# 02_USB2UART.net
KiCad netlist of a schematic drawn in Altium Designer
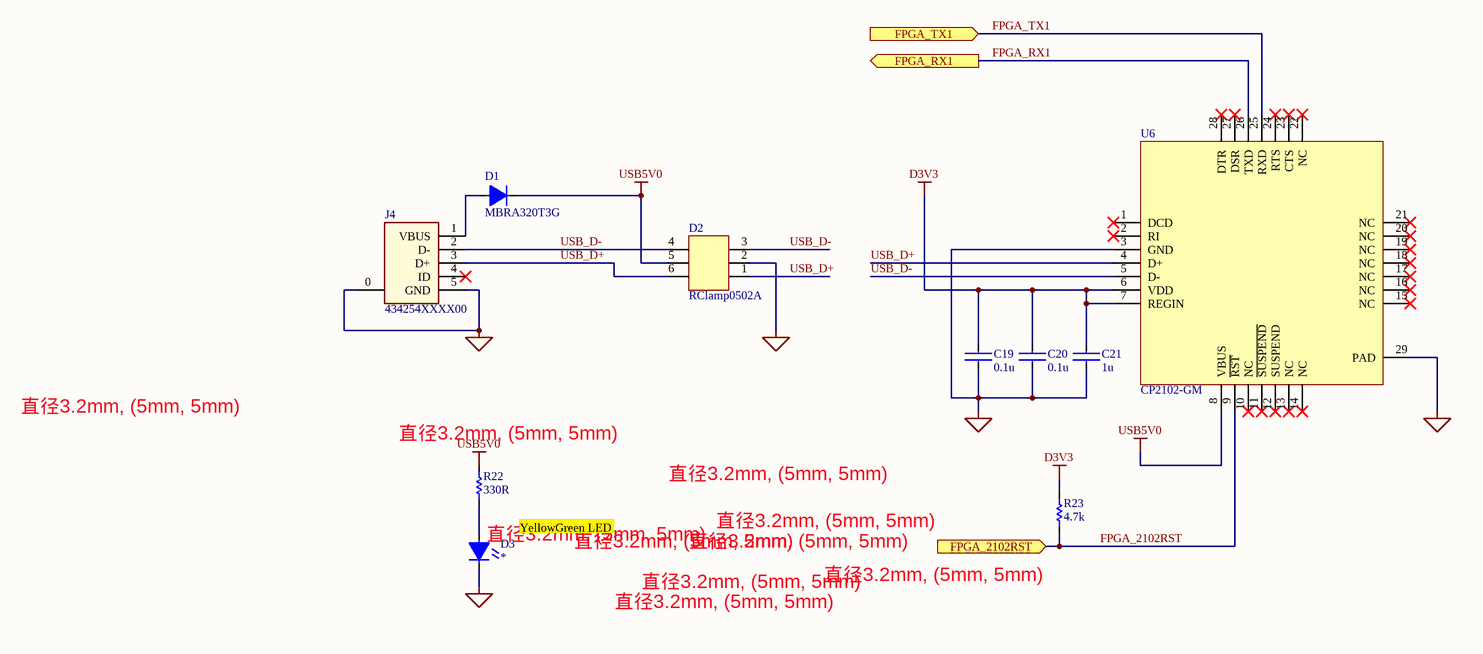
[diagram p0: 02_USB2UART.SchDoc]

(export (version "E")
  (design (tool "Eeschema 10.0.6"))
  (components
    (comp (ref "C19")
      (value "0.1u")
      (footprint "C0402")
      (description "CAP,Ceramic,X7R,10%,16V,0.1uF,0402")
      (libsource (lib "AD15_libpkg") (part "CAP011"))
    )
    (comp (ref "C20")
      (value "0.1u")
      (footprint "C0402")
      (description "CAP,Ceramic,X7R,10%,16V,0.1uF,0402")
      (libsource (lib "AD15_libpkg") (part "CAP011"))
    )
    (comp (ref "C21")
      (value "1u")
      (footprint "CAPC1608X09N_C0603")
      (description "CAP,Ceramic,X7R,10%,16V,1uF,0603")
      (libsource (lib "AD15_libpkg") (part "CAP12"))
    )
    (comp (ref "D1")
      (value "MBRA320T3G")
      (footprint "DIOM4326X23N_SMA")
      (description "Schottky Barrier Rectifier,20V,3A,SMA")
      (libsource (lib "AD15_libpkg") (part "MBRA320T3G"))
    )
    (comp (ref "D2")
      (value "RClamp0502A")
      (footprint "SOTFL50P162X60-6N_RClamp0502A")
      (description "TVS array,0.9pF,5V,SC89")
      (libsource (lib "altium-import") (part "root_2_RClamp0502A_"))
    )
    (comp (ref "D3")
      (value "*")
      (footprint "LED0603")
      (description "LED,Yellow Green,2V,20mA,0603")
      (libsource (lib "AD15_libpkg") (part "LED YellowGreen0603"))
    )
    (comp (ref "J4")
      (value "434254XXXX00")
      (footprint "434254XXXX00")
      (description "Mini-USB Receptacle,5-Pin,0.8mm Pitch,SMD")
      (libsource (lib "AD15_libpkg") (part "434254XXXX00"))
    )
    (comp (ref "R22")
      (value "330R")
      (footprint "R0402")
      (description "RES,330R,1%,1/16W,0402")
      (libsource (lib "AD15_libpkg") (part "RES0111"))
    )
    (comp (ref "R23")
      (value "4.7k")
      (footprint "R0402")
      (description "RES,4.7k,1%,1/16W,0402")
      (libsource (lib "R0402") (part "RES015"))
    )
    (comp (ref "U6")
      (value "CP2102-GM")
      (footprint "QFN50P500X500X100_HS-29N_CP2012GM")
      (description "IC,USB to UART bridge,QFN28")
      (libsource (lib "AD15_libpkg") (part "CP2102-GM"))
    )
  )
  (nets
    (net (code "1") (name "/FPGA_2102RST") (class "Default")
      (node (ref "R23") (pin "1") (pinfunction "0_1") (pintype "passive"))
      (node (ref "U6") (pin "9") (pinfunction "~{RST}_9") (pintype "passive"))
    )
    (net (code "2") (name "/FPGA_RX1") (class "Default")
      (node (ref "U6") (pin "26") (pinfunction "TXD_26") (pintype "passive"))
    )
    (net (code "3") (name "/FPGA_TX1") (class "Default")
      (node (ref "U6") (pin "25") (pinfunction "RXD_25") (pintype "passive"))
    )
    (net (code "4") (name "/USB_D+") (class "Default")
      (node (ref "D2") (pin "1") (pinfunction "0_1") (pintype "passive"))
      (node (ref "D2") (pin "6") (pinfunction "5_6") (pintype "passive"))
      (node (ref "J4") (pin "3") (pinfunction "D+_3") (pintype "passive"))
      (node (ref "U6") (pin "4") (pinfunction "D+_4") (pintype "passive"))
    )
    (net (code "5") (name "/USB_D-") (class "Default")
      (node (ref "D2") (pin "3") (pinfunction "2_3") (pintype "passive"))
      (node (ref "D2") (pin "4") (pinfunction "3_4") (pintype "passive"))
      (node (ref "J4") (pin "2") (pinfunction "D-_2") (pintype "passive"))
      (node (ref "U6") (pin "5") (pinfunction "D-_5") (pintype "passive"))
    )
    (net (code "6") (name "D3V3") (class "Default")
      (node (ref "C19") (pin "1") (pinfunction "0_1") (pintype "passive"))
      (node (ref "C20") (pin "1") (pinfunction "0_1") (pintype "passive"))
      (node (ref "C21") (pin "1") (pinfunction "0_1") (pintype "passive"))
      (node (ref "R23") (pin "2") (pinfunction "2_2") (pintype "passive"))
      (node (ref "U6") (pin "6") (pinfunction "VDD_6") (pintype "passive"))
      (node (ref "U6") (pin "7") (pinfunction "REGIN_7") (pintype "passive"))
    )
    (net (code "7") (name "GND") (class "Default")
      (node (ref "C19") (pin "2") (pinfunction "1_2") (pintype "passive"))
      (node (ref "C20") (pin "2") (pinfunction "1_2") (pintype "passive"))
      (node (ref "C21") (pin "2") (pinfunction "1_2") (pintype "passive"))
      (node (ref "D2") (pin "2") (pinfunction "1_2") (pintype "passive"))
      (node (ref "D3") (pin "2") (pinfunction "L21_2") (pintype "passive"))
      (node (ref "J4") (pin "0") (pintype "passive"))
      (node (ref "J4") (pin "5") (pinfunction "GND_5") (pintype "passive"))
      (node (ref "U6") (pin "29") (pinfunction "PAD_29") (pintype "passive"))
      (node (ref "U6") (pin "3") (pinfunction "GND_3") (pintype "passive"))
    )
    (net (code "8") (name "Net-(D1-A)") (class "Default")
      (node (ref "D1") (pin "1") (pinfunction "A_1") (pintype "passive"))
      (node (ref "J4") (pin "1") (pinfunction "VBUS_1") (pintype "passive"))
    )
    (net (code "9") (name "Net-(D3-L20)") (class "Default")
      (node (ref "D3") (pin "1") (pinfunction "L20_1") (pintype "passive"))
      (node (ref "R22") (pin "1") (pinfunction "0_1") (pintype "passive"))
    )
    (net (code "10") (name "USB5V0") (class "Default")
      (node (ref "D1") (pin "2") (pinfunction "K_2") (pintype "passive"))
      (node (ref "D2") (pin "5") (pinfunction "4_5") (pintype "passive"))
      (node (ref "R22") (pin "2") (pinfunction "2_2") (pintype "passive"))
      (node (ref "U6") (pin "8") (pinfunction "VBUS_8") (pintype "passive"))
    )
    (net (code "11") (name "unconnected-(J4-ID-Pad4)") (class "Default")
      (node (ref "J4") (pin "4") (pinfunction "ID_4") (pintype "passive+no_connect"))
    )
    (net (code "12") (name "unconnected-(U6-CTS-Pad23)") (class "Default")
      (node (ref "U6") (pin "23") (pinfunction "CTS_23") (pintype "passive+no_connect"))
    )
    (net (code "13") (name "unconnected-(U6-DCD-Pad1)") (class "Default")
      (node (ref "U6") (pin "1") (pinfunction "DCD_1") (pintype "passive+no_connect"))
    )
    (net (code "14") (name "unconnected-(U6-DSR-Pad27)") (class "Default")
      (node (ref "U6") (pin "27") (pinfunction "DSR_27") (pintype "passive+no_connect"))
    )
    (net (code "15") (name "unconnected-(U6-DTR-Pad28)") (class "Default")
      (node (ref "U6") (pin "28") (pinfunction "DTR_28") (pintype "passive+no_connect"))
    )
    (net (code "16") (name "unconnected-(U6-NC-Pad10)") (class "Default")
      (node (ref "U6") (pin "10") (pinfunction "NC_10") (pintype "passive+no_connect"))
    )
    (net (code "17") (name "unconnected-(U6-NC-Pad13)") (class "Default")
      (node (ref "U6") (pin "13") (pinfunction "NC_13") (pintype "passive+no_connect"))
    )
    (net (code "18") (name "unconnected-(U6-NC-Pad14)") (class "Default")
      (node (ref "U6") (pin "14") (pinfunction "NC_14") (pintype "passive+no_connect"))
    )
    (net (code "19") (name "unconnected-(U6-NC-Pad15)") (class "Default")
      (node (ref "U6") (pin "15") (pinfunction "NC_15") (pintype "passive+no_connect"))
    )
    (net (code "20") (name "unconnected-(U6-NC-Pad16)") (class "Default")
      (node (ref "U6") (pin "16") (pinfunction "NC_16") (pintype "passive+no_connect"))
    )
    (net (code "21") (name "unconnected-(U6-NC-Pad17)") (class "Default")
      (node (ref "U6") (pin "17") (pinfunction "NC_17") (pintype "passive+no_connect"))
    )
    (net (code "22") (name "unconnected-(U6-NC-Pad18)") (class "Default")
      (node (ref "U6") (pin "18") (pinfunction "NC_18") (pintype "passive+no_connect"))
    )
    (net (code "23") (name "unconnected-(U6-NC-Pad19)") (class "Default")
      (node (ref "U6") (pin "19") (pinfunction "NC_19") (pintype "passive+no_connect"))
    )
    (net (code "24") (name "unconnected-(U6-NC-Pad20)") (class "Default")
      (node (ref "U6") (pin "20") (pinfunction "NC_20") (pintype "passive+no_connect"))
    )
    (net (code "25") (name "unconnected-(U6-NC-Pad21)") (class "Default")
      (node (ref "U6") (pin "21") (pinfunction "NC_21") (pintype "passive+no_connect"))
    )
    (net (code "26") (name "unconnected-(U6-NC-Pad22)") (class "Default")
      (node (ref "U6") (pin "22") (pinfunction "NC_22") (pintype "passive+no_connect"))
    )
    (net (code "27") (name "unconnected-(U6-RI-Pad2)") (class "Default")
      (node (ref "U6") (pin "2") (pinfunction "RI_2") (pintype "passive+no_connect"))
    )
    (net (code "28") (name "unconnected-(U6-RTS-Pad24)") (class "Default")
      (node (ref "U6") (pin "24") (pinfunction "RTS_24") (pintype "passive+no_connect"))
    )
    (net (code "29") (name "unconnected-(U6-SUSPEND-Pad12)") (class "Default")
      (node (ref "U6") (pin "12") (pinfunction "SUSPEND_12") (pintype "passive+no_connect"))
    )
    (net (code "30") (name "unconnected-(U6-~{SUSPEND}-Pad11)") (class "Default")
      (node (ref "U6") (pin "11") (pinfunction "~{SUSPEND}_11") (pintype "passive+no_connect"))
    )
  )
)
